# Schematic.net
KiCad netlist of a schematic drawn in EAGLE
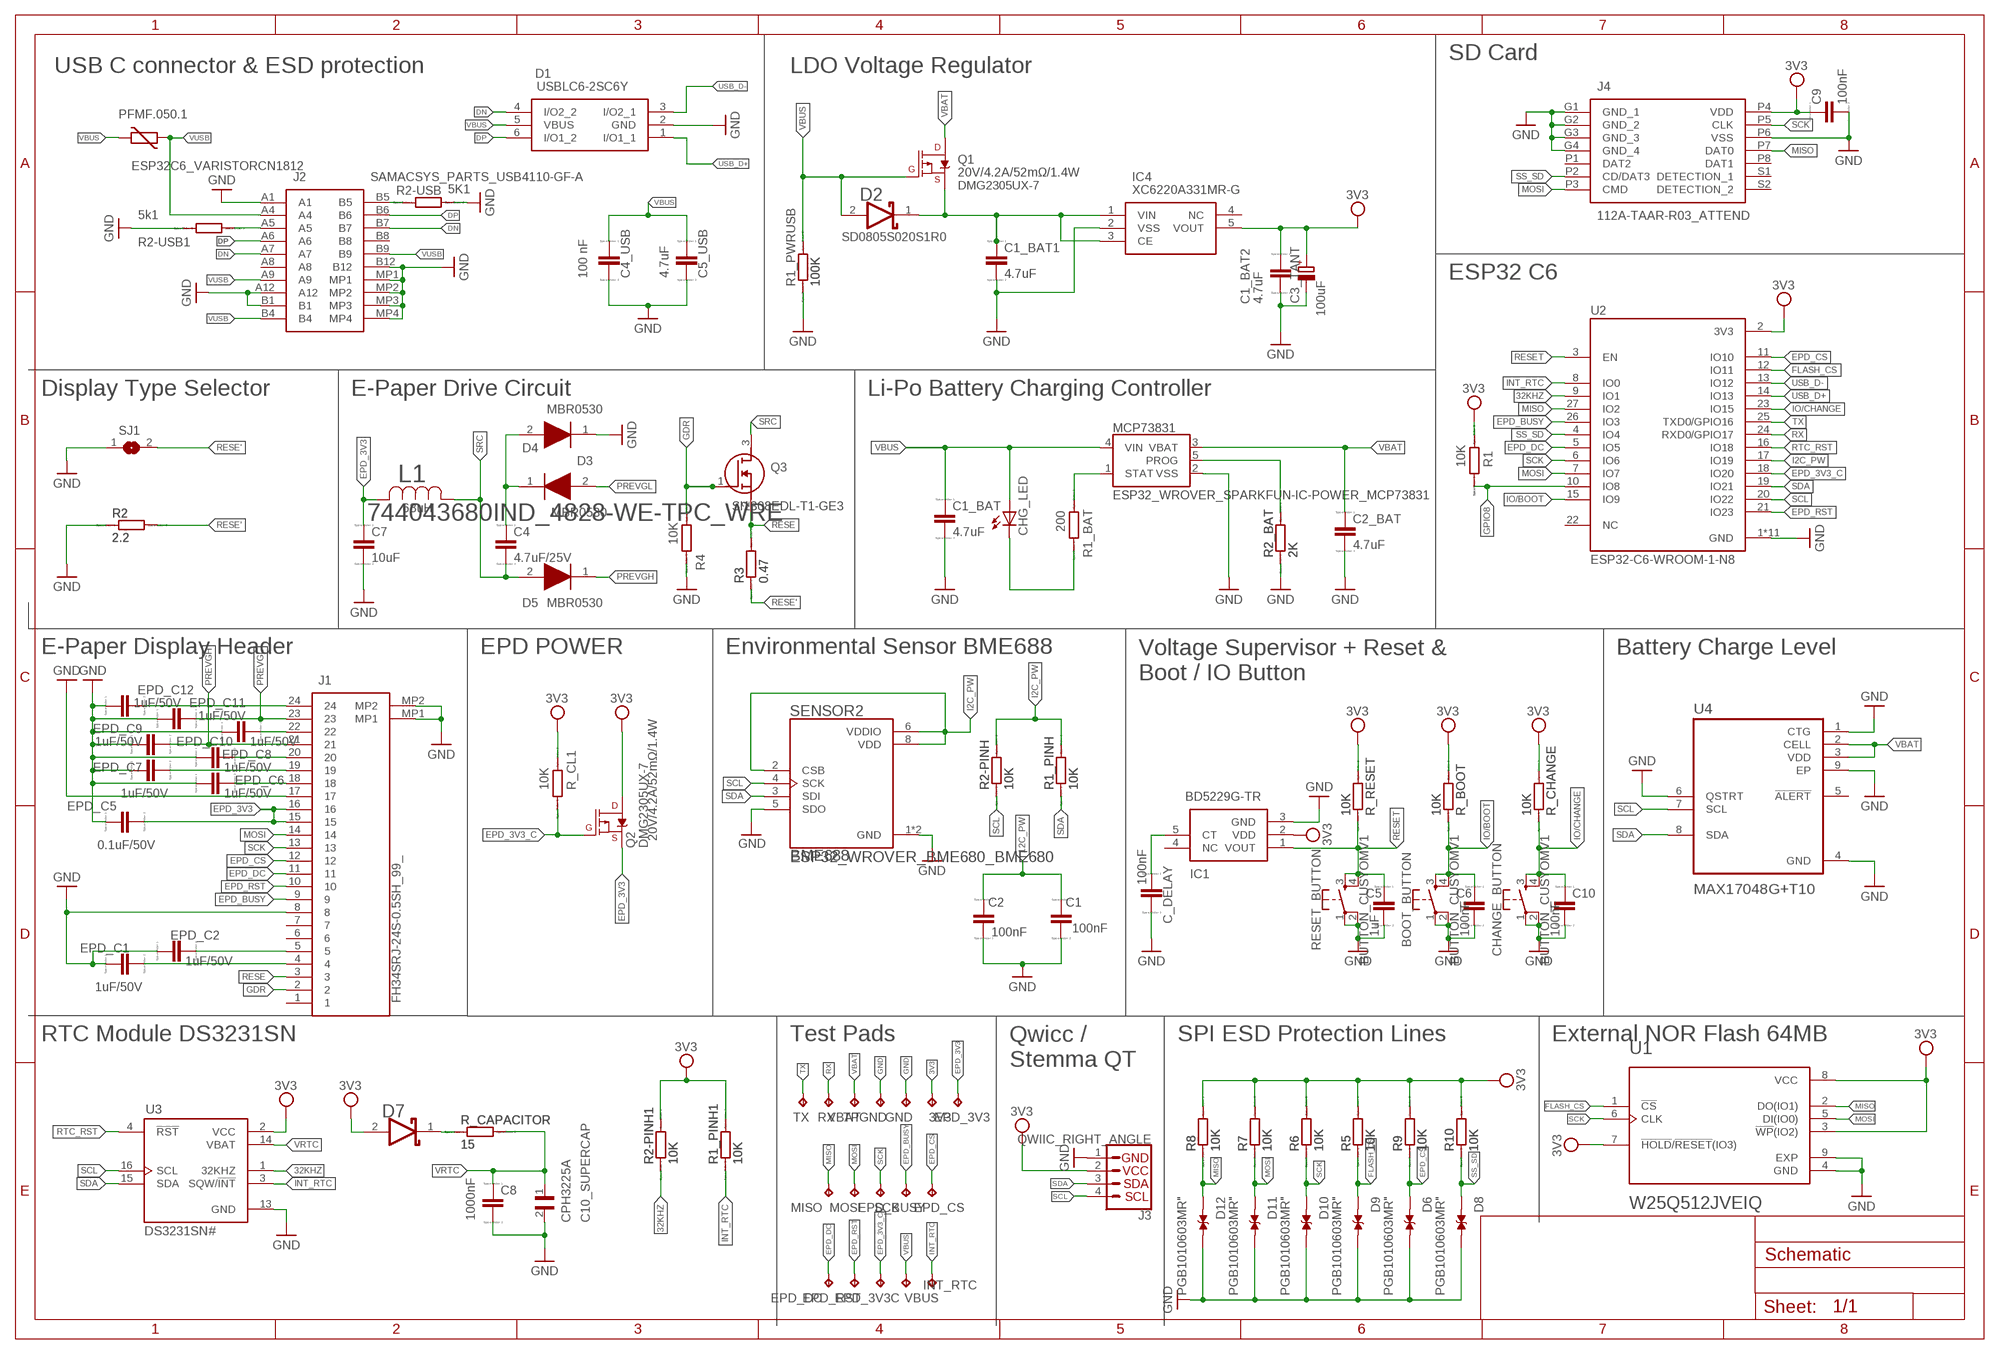
[diagram p0: schematic, sheet 1]

(export (version "E")
  (design (tool "Eeschema 10.0.6"))
  (components
    (comp (ref "3V3")
      (value "TPTP20R")
      (footprint "eagle-import:TP20R")
      (libsource (lib "eagle-import") (part "TPTP20R"))
    )
    (comp (ref "BOOT_BUTTON")
      (value "BUTTON_CUSYOMV1")
      (footprint "eagle-import:MYBUTTON")
      (libsource (lib "eagle-import") (part "BUTTON_CUSYOMV1"))
    )
    (comp (ref "C1")
      (value "100nF")
      (footprint "eagle-import:ESP32_WROVER_EAGLE-LTSPICE_C0402")
      (libsource (lib "eagle-import") (part "ESP32_WROVER_EAGLE-LTSPICE_CC0402"))
    )
    (comp (ref "C1_BAT")
      (value "4.7uF")
      (footprint "eagle-import:EAGLE-LTSPICE_C0402")
      (libsource (lib "eagle-import") (part "EAGLE-LTSPICE_CC0402"))
    )
    (comp (ref "C1_BAT1")
      (value "4.7uF")
      (footprint "eagle-import:EAGLE-LTSPICE_C0402")
      (libsource (lib "eagle-import") (part "EAGLE-LTSPICE_CC0402"))
    )
    (comp (ref "C1_BAT2")
      (value "4.7uF")
      (footprint "eagle-import:EAGLE-LTSPICE_C0402")
      (libsource (lib "eagle-import") (part "EAGLE-LTSPICE_CC0402"))
    )
    (comp (ref "C2")
      (value "100nF")
      (footprint "eagle-import:ESP32_WROVER_EAGLE-LTSPICE_C0402")
      (libsource (lib "eagle-import") (part "ESP32_WROVER_EAGLE-LTSPICE_CC0402"))
    )
    (comp (ref "C2_BAT")
      (value "4.7uF")
      (footprint "eagle-import:EAGLE-LTSPICE_C0402")
      (libsource (lib "eagle-import") (part "EAGLE-LTSPICE_CC0402"))
    )
    (comp (ref "C3_TANT")
      (value "100uF")
      (footprint "eagle-import:RCL_CT3528")
      (libsource (lib "eagle-import") (part "RCL_CPOL-EUCT3528"))
    )
    (comp (ref "C4")
      (value "4.7uF/25V")
      (footprint "eagle-import:EAGLE-LTSPICE_C0402")
      (libsource (lib "eagle-import") (part "EAGLE-LTSPICE_CC0402"))
    )
    (comp (ref "C4_USB")
      (value "100 nF")
      (footprint "eagle-import:ESP32_WROVER_EAGLE-LTSPICE_C0402")
      (libsource (lib "eagle-import") (part "ESP32_WROVER_EAGLE-LTSPICE_CC0402"))
    )
    (comp (ref "C5")
      (value "1uF")
      (footprint "eagle-import:EAGLE-LTSPICE_C0402")
      (libsource (lib "eagle-import") (part "EAGLE-LTSPICE_CC0402"))
    )
    (comp (ref "C5_USB")
      (value "4.7uF")
      (footprint "eagle-import:ESP32_WROVER_EAGLE-LTSPICE_C0402")
      (libsource (lib "eagle-import") (part "ESP32_WROVER_EAGLE-LTSPICE_CC0402"))
    )
    (comp (ref "C6")
      (value "100nF")
      (footprint "eagle-import:EAGLE-LTSPICE_C0402")
      (libsource (lib "eagle-import") (part "EAGLE-LTSPICE_CC0402"))
    )
    (comp (ref "C7")
      (value "10uF")
      (footprint "eagle-import:EAGLE-LTSPICE_C0402")
      (libsource (lib "eagle-import") (part "EAGLE-LTSPICE_CC0402"))
    )
    (comp (ref "C8")
      (value "1000nF")
      (footprint "eagle-import:EAGLE-LTSPICE_C0402")
      (libsource (lib "eagle-import") (part "EAGLE-LTSPICE_CC0402"))
    )
    (comp (ref "C9")
      (value "100nF")
      (footprint "eagle-import:EAGLE-LTSPICE_C0402")
      (libsource (lib "eagle-import") (part "EAGLE-LTSPICE_CC0402"))
    )
    (comp (ref "C10")
      (value "100nF")
      (footprint "eagle-import:EAGLE-LTSPICE_C0402")
      (libsource (lib "eagle-import") (part "EAGLE-LTSPICE_CC0402"))
    )
    (comp (ref "C10_SUPERCAP")
      (value "CPH3225A")
      (footprint "eagle-import:CAPCP3225X100N")
      (fields (field (name "MF") "Seiko Instruments"))
      (libsource (lib "eagle-import") (part "CPH3225A"))
    )
    (comp (ref "CHANGE_BUTTON")
      (value "BUTTON_CUSYOMV1")
      (footprint "eagle-import:MYBUTTON")
      (libsource (lib "eagle-import") (part "BUTTON_CUSYOMV1"))
    )
    (comp (ref "CHG_LED")
      (value "ADAFRUIT_LEDCHIP-LED0603")
      (footprint "eagle-import:ADAFRUIT_CHIP-LED0603")
      (libsource (lib "eagle-import") (part "ADAFRUIT_LEDCHIP-LED0603"))
    )
    (comp (ref "C_DELAY")
      (value "100nF")
      (footprint "eagle-import:EAGLE-LTSPICE_C0402")
      (libsource (lib "eagle-import") (part "EAGLE-LTSPICE_CC0402"))
    )
    (comp (ref "D1")
      (value "USBLC6-2SC6Y")
      (footprint "eagle-import:SOT95P280X145-6N")
      (fields (field (name "MF") "STMicroelectronics"))
      (libsource (lib "eagle-import") (part "USBLC6-2SC6Y"))
    )
    (comp (ref "D2")
      (value "ESP32_WROVER_AVX---SD0805S020S1R0_AVX_SD0805S020S1R0_0_0AVX_SD0805S020S1R0_0_0")
      (footprint "eagle-import:ESP32_WROVER_AVX---SD0805S020S1R0_AVX_SD0805S020S1R0_0")
      (fields
        (field (name "DIGIKEY_PART_NUMBER") "478-7800-1-ND")
        (field (name "MF") "AVX")
        (field (name "MOUSER_PART_NUMBER") "581-SD0805S020S1R0")
      )
      (libsource (lib "eagle-import") (part "ESP32_WROVER_AVX---SD0805S020S1R0_AVX_SD0805S020S1R0_0_0AVX_SD0805S020S1R0_0_0"))
    )
    (comp (ref "D3")
      (value "MBR0530")
      (footprint "eagle-import:SOD3716X135N")
      (fields (field (name "MF") "ON Semiconductor"))
      (libsource (lib "eagle-import") (part "MBR0530"))
    )
    (comp (ref "D4")
      (value "MBR0530")
      (footprint "eagle-import:SOD3716X135N")
      (fields (field (name "MF") "ON Semiconductor"))
      (libsource (lib "eagle-import") (part "MBR0530"))
    )
    (comp (ref "D5")
      (value "MBR0530")
      (footprint "eagle-import:SOD3716X135N")
      (fields (field (name "MF") "ON Semiconductor"))
      (libsource (lib "eagle-import") (part "MBR0530"))
    )
    (comp (ref "D6")
      (value "PGB1010603MR\"")
      (footprint "eagle-import:DIOC1608X36N")
      (libsource (lib "eagle-import") (part "PGB1010603MR{dblquote}"))
    )
    (comp (ref "D7")
      (value "ESP32_WROVER_AVX---SD0805S020S1R0_AVX_SD0805S020S1R0_0_0AVX_SD0805S020S1R0_0_0")
      (footprint "eagle-import:ESP32_WROVER_AVX---SD0805S020S1R0_AVX_SD0805S020S1R0_0")
      (fields
        (field (name "DIGIKEY_PART_NUMBER") "478-7800-1-ND")
        (field (name "MF") "AVX")
        (field (name "MOUSER_PART_NUMBER") "581-SD0805S020S1R0")
      )
      (libsource (lib "eagle-import") (part "ESP32_WROVER_AVX---SD0805S020S1R0_AVX_SD0805S020S1R0_0_0AVX_SD0805S020S1R0_0_0"))
    )
    (comp (ref "D8")
      (value "PGB1010603MR\"")
      (footprint "eagle-import:DIOC1608X36N")
      (libsource (lib "eagle-import") (part "PGB1010603MR{dblquote}"))
    )
    (comp (ref "D9")
      (value "PGB1010603MR\"")
      (footprint "eagle-import:DIOC1608X36N")
      (libsource (lib "eagle-import") (part "PGB1010603MR{dblquote}"))
    )
    (comp (ref "D10")
      (value "PGB1010603MR\"")
      (footprint "eagle-import:DIOC1608X36N")
      (libsource (lib "eagle-import") (part "PGB1010603MR{dblquote}"))
    )
    (comp (ref "D11")
      (value "PGB1010603MR\"")
      (footprint "eagle-import:DIOC1608X36N")
      (libsource (lib "eagle-import") (part "PGB1010603MR{dblquote}"))
    )
    (comp (ref "D12")
      (value "PGB1010603MR\"")
      (footprint "eagle-import:DIOC1608X36N")
      (libsource (lib "eagle-import") (part "PGB1010603MR{dblquote}"))
    )
    (comp (ref "EPD_3V3")
      (value "TPTP20R")
      (footprint "eagle-import:TP20R")
      (libsource (lib "eagle-import") (part "TPTP20R"))
    )
    (comp (ref "EPD_3V3C")
      (value "TPTP20R")
      (footprint "eagle-import:TP20R")
      (libsource (lib "eagle-import") (part "TPTP20R"))
    )
    (comp (ref "EPD_BUSY")
      (value "TPTP20R")
      (footprint "eagle-import:TP20R")
      (libsource (lib "eagle-import") (part "TPTP20R"))
    )
    (comp (ref "EPD_C1")
      (value "1uF/50V")
      (footprint "eagle-import:EAGLE-LTSPICE_C0402")
      (libsource (lib "eagle-import") (part "EAGLE-LTSPICE_CC0402"))
    )
    (comp (ref "EPD_C2")
      (value "1uF/50V")
      (footprint "eagle-import:EAGLE-LTSPICE_C0402")
      (libsource (lib "eagle-import") (part "EAGLE-LTSPICE_CC0402"))
    )
    (comp (ref "EPD_C5")
      (value "0.1uF/50V")
      (footprint "eagle-import:EAGLE-LTSPICE_C0402")
      (libsource (lib "eagle-import") (part "EAGLE-LTSPICE_CC0402"))
    )
    (comp (ref "EPD_C6")
      (value "1uF/50V")
      (footprint "eagle-import:EAGLE-LTSPICE_C0402")
      (libsource (lib "eagle-import") (part "EAGLE-LTSPICE_CC0402"))
    )
    (comp (ref "EPD_C7")
      (value "1uF/50V")
      (footprint "eagle-import:EAGLE-LTSPICE_C0402")
      (libsource (lib "eagle-import") (part "EAGLE-LTSPICE_CC0402"))
    )
    (comp (ref "EPD_C8")
      (value "1uF/50V")
      (footprint "eagle-import:EAGLE-LTSPICE_C0402")
      (libsource (lib "eagle-import") (part "EAGLE-LTSPICE_CC0402"))
    )
    (comp (ref "EPD_C9")
      (value "1uF/50V")
      (footprint "eagle-import:EAGLE-LTSPICE_C0402")
      (libsource (lib "eagle-import") (part "EAGLE-LTSPICE_CC0402"))
    )
    (comp (ref "EPD_C10")
      (value "1uF/50V")
      (footprint "eagle-import:EAGLE-LTSPICE_C0402")
      (libsource (lib "eagle-import") (part "EAGLE-LTSPICE_CC0402"))
    )
    (comp (ref "EPD_C11")
      (value "1uF/50V")
      (footprint "eagle-import:EAGLE-LTSPICE_C0402")
      (libsource (lib "eagle-import") (part "EAGLE-LTSPICE_CC0402"))
    )
    (comp (ref "EPD_C12")
      (value "1uF/50V")
      (footprint "eagle-import:EAGLE-LTSPICE_C0402")
      (libsource (lib "eagle-import") (part "EAGLE-LTSPICE_CC0402"))
    )
    (comp (ref "EPD_CS")
      (value "TPTP20R")
      (footprint "eagle-import:TP20R")
      (libsource (lib "eagle-import") (part "TPTP20R"))
    )
    (comp (ref "EPD_DC")
      (value "TPTP20R")
      (footprint "eagle-import:TP20R")
      (libsource (lib "eagle-import") (part "TPTP20R"))
    )
    (comp (ref "EPD_RST")
      (value "TPTP20R")
      (footprint "eagle-import:TP20R")
      (libsource (lib "eagle-import") (part "TPTP20R"))
    )
    (comp (ref "GND")
      (value "TPTP20R")
      (footprint "eagle-import:TP20R")
      (libsource (lib "eagle-import") (part "TPTP20R"))
    )
    (comp (ref "IC1")
      (value "BD5229G-TR")
      (footprint "eagle-import:SOT95P280X125-5N")
      (fields (field (name "MOUSER_PART_NUMBER") "755-BD5229G-TR"))
      (libsource (lib "eagle-import") (part "BD5229G-TR"))
    )
    (comp (ref "IC4")
      (value "XC6220A331MR-G")
      (footprint "eagle-import:SOT95P280X120-5N")
      (fields (field (name "MOUSER_PART_NUMBER") "865-XC6220A331MR-G"))
      (libsource (lib "eagle-import") (part "XC6220A331MR-G"))
    )
    (comp (ref "INT_RTC")
      (value "TPTP20R")
      (footprint "eagle-import:TP20R")
      (libsource (lib "eagle-import") (part "TPTP20R"))
    )
    (comp (ref "J1")
      (value "FH34SRJ-24S-0.5SH_99_")
      (footprint "eagle-import:FH34SRJ24S05SH99")
      (fields
        (field (name "MANUFACTURER_PART_NUMBER") "FH34SRJ-24S-0.5SH(99)")
        (field (name "MOUSER_PART_NUMBER") "798-FH34SRJ24S05SH99")
      )
      (libsource (lib "eagle-import") (part "FH34SRJ-24S-0.5SH_99_"))
    )
    (comp (ref "J2")
      (value "SAMACSYS_PARTS_USB4110-GF-A")
      (footprint "eagle-import:SAMACSYS_PARTS_USB4110GFA")
      (fields
        (field (name "MANUFACTURER_PART_NUMBER") "USB4110-GF-A")
        (field (name "MOUSER_PART_NUMBER") "640-USB4110-GF-A")
      )
      (libsource (lib "eagle-import") (part "SAMACSYS_PARTS_USB4110-GF-A"))
    )
    (comp (ref "J3")
      (value "QWIIC_RIGHT_ANGLE")
      (footprint "eagle-import:JST04_1MM_RA")
      (libsource (lib "eagle-import") (part "QWIIC_CONNECTORJS-1MM"))
    )
    (comp (ref "J4")
      (value "112A-TAAR-R03_ATTEND")
      (footprint "eagle-import:112ATAARR03ATTEND")
      (fields (field (name "MANUFACTURER_PART_NUMBER") "112A-TAAR-R03 ATTEND"))
      (libsource (lib "eagle-import") (part "112A-TAAR-R03_ATTEND"))
    )
    (comp (ref "L1")
      (value "744043680IND_4828-WE-TPC_WRE")
      (footprint "eagle-import:IND_4828-WE-TPC_WRE")
      (fields
        (field (name "MANUFACTURER_PART_NUMBER") "744043680")
        (field (name "L1") "68uH")
        (field (name "COPYRIGHT") "Copyright (C) 2024 Ultra Librarian. All rights reserved.")
      )
      (libsource (lib "eagle-import") (part "744043680IND_4828-WE-TPC_WRE"))
    )
    (comp (ref "MCP73831")
      (value "ESP32_WROVER_SPARKFUN-IC-POWER_MCP73831")
      (footprint "eagle-import:ESP32_WROVER_SPARKFUN-IC-POWER_SOT23-5")
      (libsource (lib "eagle-import") (part "ESP32_WROVER_SPARKFUN-IC-POWER_MCP73831"))
    )
    (comp (ref "MISO")
      (value "TPTP20R")
      (footprint "eagle-import:TP20R")
      (libsource (lib "eagle-import") (part "TPTP20R"))
    )
    (comp (ref "MOSI")
      (value "TPTP20R")
      (footprint "eagle-import:TP20R")
      (libsource (lib "eagle-import") (part "TPTP20R"))
    )
    (comp (ref "PFMF.050.1")
      (value "ESP32C6_VARISTORCN1812")
      (footprint "eagle-import:ESP32C6_VARISTOR_CT_CN1812")
      (libsource (lib "eagle-import") (part "ESP32C6_VARISTORCN1812"))
    )
    (comp (ref "Q1")
      (value "20V/4.2A/52mΩ/1.4W")
      (footprint "eagle-import:ESP32_WROVER_SPARKFUN-DISCRETESEMI_SOT23-3")
      (libsource (lib "eagle-import") (part "ESP32_WROVER_SPARKFUN-DISCRETESEMI_MOSFET_PCH-DMG2305UX-7"))
    )
    (comp (ref "Q2")
      (value "20V/4.2A/52mΩ/1.4W")
      (footprint "eagle-import:ESP32_WROVER_SPARKFUN-DISCRETESEMI_SOT23-3")
      (libsource (lib "eagle-import") (part "ESP32_WROVER_SPARKFUN-DISCRETESEMI_MOSFET_PCH-DMG2305UX-7"))
    )
    (comp (ref "Q3")
      (value "SI1308EDL-T1-GE3")
      (footprint "eagle-import:SOT65P210X110-3N")
      (fields (field (name "MF") "Vishay Siliconix"))
      (libsource (lib "eagle-import") (part "SI1308EDL-T1-GE3"))
    )
    (comp (ref "R1")
      (value "10K")
      (footprint "eagle-import:ESP32_WROVER_EAGLE-LTSPICE_R0402")
      (libsource (lib "eagle-import") (part "ESP32_WROVER_EAGLE-LTSPICE_RR0402"))
    )
    (comp (ref "R1_BAT")
      (value "200")
      (footprint "eagle-import:ESP32_WROVER_EAGLE-LTSPICE_R0402")
      (libsource (lib "eagle-import") (part "ESP32_WROVER_EAGLE-LTSPICE_RR0402"))
    )
    (comp (ref "R1_PINH")
      (value "10K")
      (footprint "eagle-import:ESP32_WROVER_EAGLE-LTSPICE_R0402")
      (libsource (lib "eagle-import") (part "ESP32_WROVER_EAGLE-LTSPICE_RR0402"))
    )
    (comp (ref "R1_PINH1")
      (value "10K")
      (footprint "eagle-import:ESP32_WROVER_EAGLE-LTSPICE_R0402")
      (libsource (lib "eagle-import") (part "ESP32_WROVER_EAGLE-LTSPICE_RR0402"))
    )
    (comp (ref "R1_PWRUSB")
      (value "100K")
      (footprint "eagle-import:ESP32_WROVER_EAGLE-LTSPICE_R0402")
      (libsource (lib "eagle-import") (part "ESP32_WROVER_EAGLE-LTSPICE_RR0402"))
    )
    (comp (ref "R2")
      (value "2.2")
      (footprint "eagle-import:ESP32_WROVER_EAGLE-LTSPICE_R0402")
      (libsource (lib "eagle-import") (part "ESP32_WROVER_EAGLE-LTSPICE_RR0402"))
    )
    (comp (ref "R2-PINH")
      (value "10K")
      (footprint "eagle-import:ESP32_WROVER_EAGLE-LTSPICE_R0402")
      (libsource (lib "eagle-import") (part "ESP32_WROVER_EAGLE-LTSPICE_RR0402"))
    )
    (comp (ref "R2-PINH1")
      (value "10K")
      (footprint "eagle-import:ESP32_WROVER_EAGLE-LTSPICE_R0402")
      (libsource (lib "eagle-import") (part "ESP32_WROVER_EAGLE-LTSPICE_RR0402"))
    )
    (comp (ref "R2-USB")
      (value "5K1")
      (footprint "eagle-import:ESP32_WROVER_EAGLE-LTSPICE_R0402")
      (libsource (lib "eagle-import") (part "ESP32_WROVER_EAGLE-LTSPICE_RR0402"))
    )
    (comp (ref "R2-USB1")
      (value "5k1")
      (footprint "eagle-import:ESP32_WROVER_EAGLE-LTSPICE_R0402")
      (libsource (lib "eagle-import") (part "ESP32_WROVER_EAGLE-LTSPICE_RR0402"))
    )
    (comp (ref "R2_BAT")
      (value "2K")
      (footprint "eagle-import:ESP32_WROVER_EAGLE-LTSPICE_R0402")
      (libsource (lib "eagle-import") (part "ESP32_WROVER_EAGLE-LTSPICE_RR0402"))
    )
    (comp (ref "R3")
      (value "0.47")
      (footprint "eagle-import:ESP32_WROVER_EAGLE-LTSPICE_R0402")
      (libsource (lib "eagle-import") (part "ESP32_WROVER_EAGLE-LTSPICE_RR0402"))
    )
    (comp (ref "R4")
      (value "10K")
      (footprint "eagle-import:ESP32_WROVER_EAGLE-LTSPICE_R0402")
      (libsource (lib "eagle-import") (part "ESP32_WROVER_EAGLE-LTSPICE_RR0402"))
    )
    (comp (ref "R5")
      (value "10K")
      (footprint "eagle-import:ESP32_WROVER_EAGLE-LTSPICE_R0402")
      (libsource (lib "eagle-import") (part "ESP32_WROVER_EAGLE-LTSPICE_RR0402"))
    )
    (comp (ref "R6")
      (value "10K")
      (footprint "eagle-import:ESP32_WROVER_EAGLE-LTSPICE_R0402")
      (libsource (lib "eagle-import") (part "ESP32_WROVER_EAGLE-LTSPICE_RR0402"))
    )
    (comp (ref "R7")
      (value "10K")
      (footprint "eagle-import:ESP32_WROVER_EAGLE-LTSPICE_R0402")
      (libsource (lib "eagle-import") (part "ESP32_WROVER_EAGLE-LTSPICE_RR0402"))
    )
    (comp (ref "R8")
      (value "10K")
      (footprint "eagle-import:ESP32_WROVER_EAGLE-LTSPICE_R0402")
      (libsource (lib "eagle-import") (part "ESP32_WROVER_EAGLE-LTSPICE_RR0402"))
    )
    (comp (ref "R9")
      (value "10K")
      (footprint "eagle-import:ESP32_WROVER_EAGLE-LTSPICE_R0402")
      (libsource (lib "eagle-import") (part "ESP32_WROVER_EAGLE-LTSPICE_RR0402"))
    )
    (comp (ref "R10")
      (value "10K")
      (footprint "eagle-import:ESP32_WROVER_EAGLE-LTSPICE_R0402")
      (libsource (lib "eagle-import") (part "ESP32_WROVER_EAGLE-LTSPICE_RR0402"))
    )
    (comp (ref "RESET_BUTTON")
      (value "BUTTON_CUSYOMV1")
      (footprint "eagle-import:MYBUTTON")
      (libsource (lib "eagle-import") (part "BUTTON_CUSYOMV1"))
    )
    (comp (ref "RX")
      (value "TPTP20R")
      (footprint "eagle-import:TP20R")
      (libsource (lib "eagle-import") (part "TPTP20R"))
    )
    (comp (ref "R_BOOT")
      (value "10K")
      (footprint "eagle-import:ESP32_WROVER_EAGLE-LTSPICE_R0402")
      (libsource (lib "eagle-import") (part "ESP32_WROVER_EAGLE-LTSPICE_RR0402"))
    )
    (comp (ref "R_CAPACITOR")
      (value "15")
      (footprint "eagle-import:ESP32_WROVER_EAGLE-LTSPICE_R0402")
      (libsource (lib "eagle-import") (part "ESP32_WROVER_EAGLE-LTSPICE_RR0402"))
    )
    (comp (ref "R_CHANGE")
      (value "10K")
      (footprint "eagle-import:ESP32_WROVER_EAGLE-LTSPICE_R0402")
      (libsource (lib "eagle-import") (part "ESP32_WROVER_EAGLE-LTSPICE_RR0402"))
    )
    (comp (ref "R_CL1")
      (value "10K")
      (footprint "eagle-import:ESP32_WROVER_EAGLE-LTSPICE_R0402")
      (libsource (lib "eagle-import") (part "ESP32_WROVER_EAGLE-LTSPICE_RR0402"))
    )
    (comp (ref "R_RESET")
      (value "10K")
      (footprint "eagle-import:ESP32_WROVER_EAGLE-LTSPICE_R0402")
      (libsource (lib "eagle-import") (part "ESP32_WROVER_EAGLE-LTSPICE_RR0402"))
    )
    (comp (ref "SCK")
      (value "TPTP20R")
      (footprint "eagle-import:TP20R")
      (libsource (lib "eagle-import") (part "TPTP20R"))
    )
    (comp (ref "SENSOR2")
      (value "ESP32_WROVER_BME680_BME680")
      (footprint "eagle-import:ESP32_WROVER_BME680_PSON80P300X300X100-8N")
      (fields (field (name "MF") "Bosch Sensortec") (field (name "MP") "BME680"))
      (libsource (lib "eagle-import") (part "ESP32_WROVER_BME680_BME680"))
    )
    (comp (ref "SJ1") (value "SJ") (footprint "eagle-import:SJ") (libsource (lib "eagle-import") (part "SJ")))
    (comp (ref "TPGND")
      (value "TPTP20R")
      (footprint "eagle-import:TP20R")
      (libsource (lib "eagle-import") (part "TPTP20R"))
    )
    (comp (ref "TX")
      (value "TPTP20R")
      (footprint "eagle-import:TP20R")
      (libsource (lib "eagle-import") (part "TPTP20R"))
    )
    (comp (ref "U1")
      (value "W25Q512JVEIQ")
      (footprint "eagle-import:SON127P600X800X80-9N")
      (fields (field (name "MF") "Winbond Electronics"))
      (libsource (lib "eagle-import") (part "W25Q512JVEIQ"))
    )
    (comp (ref "U2")
      (value "ESP32-C6-WROOM-1-N8")
      (footprint "eagle-import:XCVR_ESP32-C6-WROOM-1-N8")
      (fields (field (name "MF") "Espressif Systems"))
      (libsource (lib "eagle-import") (part "ESP32-C6-WROOM-1-N8"))
    )
    (comp (ref "U3")
      (value "DS3231SN#")
      (footprint "eagle-import:SOIC127P1032X265-16N")
      (fields (field (name "MF") "Analog Devices"))
      (libsource (lib "eagle-import") (part "DS3231SN#"))
    )
    (comp (ref "U4")
      (value "MAX17048G+T10")
      (footprint "eagle-import:SON50P200X200X80-9N")
      (fields (field (name "MF") "Analog Devices"))
      (libsource (lib "eagle-import") (part "MAX17048G+T10"))
    )
    (comp (ref "VBAT")
      (value "TPTP20R")
      (footprint "eagle-import:TP20R")
      (libsource (lib "eagle-import") (part "TPTP20R"))
    )
    (comp (ref "VBUS")
      (value "TPTP20R")
      (footprint "eagle-import:TP20R")
      (libsource (lib "eagle-import") (part "TPTP20R"))
    )
  )
  (nets
    (net (code "1") (name "/DMG2305UX-7") (class "Default")
      (node (ref "C1_BAT1") (pin "1") (pinfunction "1_1") (pintype "passive"))
      (node (ref "D2") (pin "1") (pinfunction "CATHODE_1") (pintype "bidirectional"))
      (node (ref "IC4") (pin "1") (pinfunction "VIN_1") (pintype "bidirectional"))
      (node (ref "IC4") (pin "3") (pinfunction "CE_3") (pintype "bidirectional"))
      (node (ref "Q1") (pin "2") (pinfunction "S_2") (pintype "bidirectional"))
    )
    (net (code "2") (name "3V3") (class "Default")
      (node (ref "3V3") (pin "TP") (pinfunction "TP_TP") (pintype "input"))
      (node (ref "C1_BAT2") (pin "1") (pinfunction "1_1") (pintype "passive"))
      (node (ref "C3_TANT") (pin "+") (pinfunction "+_+") (pintype "passive"))
      (node (ref "C9") (pin "1") (pinfunction "1_1") (pintype "passive"))
      (node (ref "D7") (pin "2") (pinfunction "ANODE_2") (pintype "bidirectional"))
      (node (ref "IC1") (pin "2") (pinfunction "VDD_2") (pintype "bidirectional"))
      (node (ref "IC4") (pin "5") (pinfunction "VOUT_5") (pintype "bidirectional"))
      (node (ref "J3") (pin "2") (pinfunction "2_2") (pintype "power_in"))
      (node (ref "J4") (pin "P4") (pinfunction "VDD_P4") (pintype "bidirectional"))
      (node (ref "Q2") (pin "3") (pinfunction "D_3") (pintype "bidirectional"))
      (node (ref "R1") (pin "2") (pinfunction "2_2") (pintype "passive"))
      (node (ref "R10") (pin "2") (pinfunction "2_2") (pintype "passive"))
      (node (ref "R1_PINH1") (pin "2") (pinfunction "2_2") (pintype "passive"))
      (node (ref "R2-PINH1") (pin "2") (pinfunction "2_2") (pintype "passive"))
      (node (ref "R5") (pin "2") (pinfunction "2_2") (pintype "passive"))
      (node (ref "R6") (pin "2") (pinfunction "2_2") (pintype "passive"))
      (node (ref "R7") (pin "2") (pinfunction "2_2") (pintype "passive"))
      (node (ref "R8") (pin "2") (pinfunction "2_2") (pintype "passive"))
      (node (ref "R9") (pin "2") (pinfunction "2_2") (pintype "passive"))
      (node (ref "R_BOOT") (pin "2") (pinfunction "2_2") (pintype "passive"))
      (node (ref "R_CHANGE") (pin "2") (pinfunction "2_2") (pintype "passive"))
      (node (ref "R_CL1") (pin "2") (pinfunction "2_2") (pintype "passive"))
      (node (ref "R_RESET") (pin "2") (pinfunction "2_2") (pintype "passive"))
      (node (ref "U1") (pin "3") (pinfunction "~{WP}(IO2)_3") (pintype "bidirectional"))
      (node (ref "U1") (pin "7") (pinfunction "~{HOLD}/~{RESET}(IO3)_7") (pintype "bidirectional"))
      (node (ref "U1") (pin "8") (pinfunction "VCC_8") (pintype "power_in"))
      (node (ref "U2") (pin "2") (pinfunction "3V3_2") (pintype "power_in"))
      (node (ref "U3") (pin "2") (pinfunction "VCC_2") (pintype "power_in"))
    )
    (net (code "3") (name "12C_PW") (class "Default")
      (node (ref "C1") (pin "1") (pinfunction "1_1") (pintype "passive"))
      (node (ref "C2") (pin "1") (pinfunction "1_1") (pintype "passive"))
    )
    (net (code "4") (name "32KHZ") (class "Default")
      (node (ref "R2-PINH1") (pin "1") (pinfunction "1_1") (pintype "passive"))
      (node (ref "U2") (pin "9") (pinfunction "IO1_9") (pintype "bidirectional"))
      (node (ref "U3") (pin "1") (pinfunction "32KHZ_1") (pintype "output"))
    )
    (net (code "5") (name "DN") (class "Default")
      (node (ref "D1") (pin "4") (pinfunction "I/O2_2_4") (pintype "bidirectional"))
      (node (ref "J2") (pin "A7") (pinfunction "A7_A7") (pintype "bidirectional"))
      (node (ref "J2") (pin "B7") (pinfunction "B7_B7") (pintype "bidirectional"))
    )
    (net (code "6") (name "DP") (class "Default")
      (node (ref "D1") (pin "6") (pinfunction "I/O1_2_6") (pintype "bidirectional"))
      (node (ref "J2") (pin "A6") (pinfunction "A6_A6") (pintype "bidirectional"))
      (node (ref "J2") (pin "B6") (pinfunction "B6_B6") (pintype "bidirectional"))
    )
    (net (code "7") (name "EPD_3V3") (class "Default")
      (node (ref "C7") (pin "1") (pinfunction "1_1") (pintype "passive"))
      (node (ref "EPD_3V3") (pin "TP") (pinfunction "TP_TP") (pintype "input"))
      (node (ref "EPD_C5") (pin "2") (pinfunction "2_2") (pintype "passive"))
      (node (ref "J1") (pin "15") (pinfunction "15_15") (pintype "bidirectional"))
      (node (ref "J1") (pin "16") (pinfunction "16_16") (pintype "bidirectional"))
      (node (ref "L1") (pin "2") (pinfunction "2_2") (pintype "passive"))
      (node (ref "Q2") (pin "2") (pinfunction "S_2") (pintype "bidirectional"))
    )
    (net (code "8") (name "EPD_3V3_C") (class "Default")
      (node (ref "EPD_3V3C") (pin "TP") (pinfunction "TP_TP") (pintype "input"))
      (node (ref "Q2") (pin "1") (pinfunction "G_1") (pintype "bidirectional"))
      (node (ref "R_CL1") (pin "1") (pinfunction "1_1") (pintype "passive"))
      (node (ref "U2") (pin "18") (pinfunction "IO20_18") (pintype "bidirectional"))
    )
    (net (code "9") (name "EPD_BUSY") (class "Default")
      (node (ref "EPD_BUSY") (pin "TP") (pinfunction "TP_TP") (pintype "input"))
      (node (ref "J1") (pin "9") (pinfunction "9_9") (pintype "bidirectional"))
      (node (ref "U2") (pin "26") (pinfunction "IO3_26") (pintype "bidirectional"))
    )
    (net (code "10") (name "EPD_CS") (class "Default")
      (node (ref "D6") (pin "1") (pinfunction "1_1") (pintype "passive"))
      (node (ref "EPD_CS") (pin "TP") (pinfunction "TP_TP") (pintype "input"))
      (node (ref "J1") (pin "12") (pinfunction "12_12") (pintype "bidirectional"))
      (node (ref "R9") (pin "1") (pinfunction "1_1") (pintype "passive"))
      (node (ref "U2") (pin "11") (pinfunction "IO10_11") (pintype "bidirectional"))
    )
    (net (code "11") (name "EPD_DC") (class "Default")
      (node (ref "EPD_DC") (pin "TP") (pinfunction "TP_TP") (pintype "input"))
      (node (ref "J1") (pin "11") (pinfunction "11_11") (pintype "bidirectional"))
      (node (ref "U2") (pin "5") (pinfunction "IO5_5") (pintype "bidirectional"))
    )
    (net (code "12") (name "EPD_RST") (class "Default")
      (node (ref "EPD_RST") (pin "TP") (pinfunction "TP_TP") (pintype "input"))
      (node (ref "J1") (pin "10") (pinfunction "10_10") (pintype "bidirectional"))
      (node (ref "U2") (pin "21") (pinfunction "IO23_21") (pintype "bidirectional"))
    )
    (net (code "13") (name "FLASH_CS") (class "Default")
      (node (ref "D9") (pin "1") (pinfunction "1_1") (pintype "passive"))
      (node (ref "R5") (pin "1") (pinfunction "1_1") (pintype "passive"))
      (node (ref "U1") (pin "1") (pinfunction "~{CS}_1") (pintype "input"))
      (node (ref "U2") (pin "12") (pinfunction "IO11_12") (pintype "bidirectional"))
    )
    (net (code "14") (name "GDR") (class "Default")
      (node (ref "J1") (pin "2") (pinfunction "2_2") (pintype "bidirectional"))
      (node (ref "Q3") (pin "1") (pinfunction "G_1") (pintype "bidirectional"))
      (node (ref "R4") (pin "2") (pinfunction "2_2") (pintype "passive"))
    )
    (net (code "15") (name "GND") (class "Default")
      (node (ref "BOOT_BUTTON") (pin "1") (pinfunction "1_1") (pintype "passive"))
      (node (ref "BOOT_BUTTON") (pin "2") (pinfunction "2_2") (pintype "passive"))
      (node (ref "C1") (pin "2") (pinfunction "2_2") (pintype "passive"))
      (node (ref "C10") (pin "2") (pinfunction "2_2") (pintype "passive"))
      (node (ref "C10_SUPERCAP") (pin "2") (pinfunction "2_2") (pintype "passive"))
      (node (ref "C1_BAT") (pin "2") (pinfunction "2_2") (pintype "passive"))
      (node (ref "C1_BAT1") (pin "2") (pinfunction "2_2") (pintype "passive"))
      (node (ref "C1_BAT2") (pin "2") (pinfunction "2_2") (pintype "passive"))
      (node (ref "C2") (pin "2") (pinfunction "2_2") (pintype "passive"))
      (node (ref "C2_BAT") (pin "2") (pinfunction "2_2") (pintype "passive"))
      (node (ref "C3_TANT") (pin "-") (pinfunction "-_-") (pintype "passive"))
      (node (ref "C4_USB") (pin "2") (pinfunction "2_2") (pintype "passive"))
      (node (ref "C5") (pin "2") (pinfunction "2_2") (pintype "passive"))
      (node (ref "C5_USB") (pin "2") (pinfunction "2_2") (pintype "passive"))
      (node (ref "C6") (pin "2") (pinfunction "2_2") (pintype "passive"))
      (node (ref "C7") (pin "2") (pinfunction "2_2") (pintype "passive"))
      (node (ref "C8") (pin "2") (pinfunction "2_2") (pintype "passive"))
      (node (ref "C9") (pin "2") (pinfunction "2_2") (pintype "passive"))
      (node (ref "CHANGE_BUTTON") (pin "1") (pinfunction "1_1") (pintype "passive"))
      (node (ref "CHANGE_BUTTON") (pin "2") (pinfunction "2_2") (pintype "passive"))
      (node (ref "C_DELAY") (pin "2") (pinfunction "2_2") (pintype "passive"))
      (node (ref "D1") (pin "2") (pinfunction "GND_2") (pintype "bidirectional"))
      (node (ref "D10") (pin "2") (pinfunction "2_2") (pintype "passive"))
      (node (ref "D11") (pin "2") (pinfunction "2_2") (pintype "passive"))
      (node (ref "D12") (pin "2") (pinfunction "2_2") (pintype "passive"))
      (node (ref "D4") (pin "1") (pinfunction "K_1") (pintype "bidirectional"))
      (node (ref "D6") (pin "2") (pinfunction "2_2") (pintype "passive"))
      (node (ref "D8") (pin "2") (pinfunction "2_2") (pintype "passive"))
      (node (ref "D9") (pin "2") (pinfunction "2_2") (pintype "passive"))
      (node (ref "EPD_C1") (pin "1") (pinfunction "1_1") (pintype "passive"))
      (node (ref "EPD_C10") (pin "1") (pinfunction "1_1") (pintype "passive"))
      (node (ref "EPD_C11") (pin "1") (pinfunction "1_1") (pintype "passive"))
      (node (ref "EPD_C12") (pin "1") (pinfunction "1_1") (pintype "passive"))
      (node (ref "EPD_C2") (pin "1") (pinfunction "1_1") (pintype "passive"))
      (node (ref "EPD_C5") (pin "1") (pinfunction "1_1") (pintype "passive"))
      (node (ref "EPD_C6") (pin "1") (pinfunction "1_1") (pintype "passive"))
      (node (ref "EPD_C7") (pin "1") (pinfunction "1_1") (pintype "passive"))
      (node (ref "EPD_C8") (pin "1") (pinfunction "1_1") (pintype "passive"))
      (node (ref "EPD_C9") (pin "1") (pinfunction "1_1") (pintype "passive"))
      (node (ref "GND") (pin "TP") (pinfunction "TP_TP") (pintype "input"))
      (node (ref "IC1") (pin "3") (pinfunction "GND_3") (pintype "bidirectional"))
      (node (ref "IC4") (pin "2") (pinfunction "VSS_2") (pintype "bidirectional"))
      (node (ref "J1") (pin "17") (pinfunction "17_17") (pintype "bidirectional"))
      (node (ref "J1") (pin "8") (pinfunction "8_8") (pintype "bidirectional"))
      (node (ref "J1") (pin "MP1") (pinfunction "MP1_MP1") (pintype "bidirectional"))
      (node (ref "J1") (pin "MP2") (pinfunction "MP2_MP2") (pintype "bidirectional"))
      (node (ref "J2") (pin "A1") (pinfunction "A1_A1") (pintype "bidirectional"))
      (node (ref "J2") (pin "A12") (pinfunction "A12_A12") (pintype "bidirectional"))
      (node (ref "J2") (pin "B1") (pinfunction "B1_B1") (pintype "bidirectional"))
      (node (ref "J2") (pin "B12") (pinfunction "B12_B12") (pintype "bidirectional"))
      (node (ref "J2") (pin "MP1") (pinfunction "MP1_MP1") (pintype "bidirectional"))
      (node (ref "J2") (pin "MP2") (pinfunction "MP2_MP2") (pintype "bidirectional"))
      (node (ref "J2") (pin "MP3") (pinfunction "MP3_MP3") (pintype "bidirectional"))
      (node (ref "J2") (pin "MP4") (pinfunction "MP4_MP4") (pintype "bidirectional"))
      (node (ref "J3") (pin "1") (pinfunction "1_1") (pintype "power_in"))
      (node (ref "J4") (pin "G1") (pinfunction "GND_1_G1") (pintype "bidirectional"))
      (node (ref "J4") (pin "G2") (pinfunction "GND_2_G2") (pintype "bidirectional"))
      (node (ref "J4") (pin "G3") (pinfunction "GND_3_G3") (pintype "bidirectional"))
      (node (ref "J4") (pin "G4") (pinfunction "GND_4_G4") (pintype "bidirectional"))
      (node (ref "J4") (pin "P6") (pinfunction "VSS_P6") (pintype "bidirectional"))
      (node (ref "MCP73831") (pin "2") (pinfunction "VSS_2") (pintype "power_in"))
      (node (ref "R1_PWRUSB") (pin "1") (pinfunction "1_1") (pintype "passive"))
      (node (ref "R2") (pin "1") (pinfunction "1_1") (pintype "passive"))
      (node (ref "R2-USB") (pin "2") (pinfunction "2_2") (pintype "passive"))
      (node (ref "R2-USB1") (pin "1") (pinfunction "1_1") (pintype "passive"))
      (node (ref "R2_BAT") (pin "1") (pinfunction "1_1") (pintype "passive"))
      (node (ref "R4") (pin "1") (pinfunction "1_1") (pintype "passive"))
      (node (ref "RESET_BUTTON") (pin "1") (pinfunction "1_1") (pintype "passive"))
      (node (ref "RESET_BUTTON") (pin "2") (pinfunction "2_2") (pintype "passive"))
      (node (ref "SENSOR2") (pin "1") (pinfunction "GND_1") (pintype "power_in"))
      (node (ref "SENSOR2") (pin "5") (pinfunction "SDO_5") (pintype "bidirectional"))
      (node (ref "SENSOR2") (pin "7") (pinfunction "GND_7") (pintype "power_in"))
      (node (ref "SJ1") (pin "1") (pinfunction "1_1") (pintype "passive"))
      (node (ref "TPGND") (pin "TP") (pinfunction "TP_TP") (pintype "input"))
      (node (ref "U1") (pin "4") (pinfunction "GND_4") (pintype "power_in"))
      (node (ref "U1") (pin "9") (pinfunction "EXP_9") (pintype "passive"))
      (node (ref "U2") (pin "1") (pinfunction "GND_1") (pintype "power_in"))
      (node (ref "U2") (pin "28") (pinfunction "GND_28") (pintype "power_in"))
      (node (ref "U2") (pin "29_1") (pinfunction "GND_29_1") (pintype "power_in"))
      (node (ref "U2") (pin "29_2") (pinfunction "GND_29_2") (pintype "power_in"))
      (node (ref "U2") (pin "29_3") (pinfunction "GND_29_3") (pintype "power_in"))
      (node (ref "U2") (pin "29_4") (pinfunction "GND_29_4") (pintype "power_in"))
      (node (ref "U2") (pin "29_5") (pinfunction "GND_29_5") (pintype "power_in"))
      (node (ref "U2") (pin "29_6") (pinfunction "GND_29_6") (pintype "power_in"))
      (node (ref "U2") (pin "29_7") (pinfunction "GND_29_7") (pintype "power_in"))
      (node (ref "U2") (pin "29_8") (pinfunction "GND_29_8") (pintype "power_in"))
      (node (ref "U2") (pin "29_9") (pinfunction "GND_29_9") (pintype "power_in"))
      (node (ref "U3") (pin "13") (pinfunction "GND_13") (pintype "power_in"))
      (node (ref "U4") (pin "1") (pinfunction "CTG_1") (pintype "power_in"))
      (node (ref "U4") (pin "4") (pinfunction "GND_4") (pintype "power_in"))
      (node (ref "U4") (pin "6") (pinfunction "QSTRT_6") (pintype "input"))
      (node (ref "U4") (pin "9") (pinfunction "EP_9") (pintype "power_in"))
    )
    (net (code "16") (name "GPIO8") (class "Default")
      (node (ref "R1") (pin "1") (pinfunction "1_1") (pintype "passive"))
      (node (ref "U2") (pin "10") (pinfunction "IO8_10") (pintype "bidirectional"))
    )
    (net (code "17") (name "I2C_PW") (class "Default")
      (node (ref "R1_PINH") (pin "2") (pinfunction "2_2") (pintype "passive"))
      (node (ref "R2-PINH") (pin "2") (pinfunction "2_2") (pintype "passive"))
      (node (ref "SENSOR2") (pin "2") (pinfunction "CSB_2") (pintype "input"))
      (node (ref "SENSOR2") (pin "6") (pinfunction "VDDIO_6") (pintype "power_in"))
      (node (ref "SENSOR2") (pin "8") (pinfunction "VDD_8") (pintype "power_in"))
      (node (ref "U2") (pin "17") (pinfunction "IO19_17") (pintype "bidirectional"))
    )
    (net (code "18") (name "INT_RTC") (class "Default")
      (node (ref "INT_RTC") (pin "TP") (pinfunction "TP_TP") (pintype "input"))
      (node (ref "R1_PINH1") (pin "1") (pinfunction "1_1") (pintype "passive"))
      (node (ref "U2") (pin "8") (pinfunction "IO0_8") (pintype "bidirectional"))
      (node (ref "U3") (pin "3") (pinfunction "SQW/~{INT}_3") (pintype "output"))
    )
    (net (code "19") (name "IO{slash}BOOT") (class "Default")
      (node (ref "BOOT_BUTTON") (pin "3") (pinfunction "3_3") (pintype "passive"))
      (node (ref "BOOT_BUTTON") (pin "4") (pinfunction "4_4") (pintype "passive"))
      (node (ref "C6") (pin "1") (pinfunction "1_1") (pintype "passive"))
      (node (ref "R_BOOT") (pin "1") (pinfunction "1_1") (pintype "passive"))
      (node (ref "U2") (pin "15") (pinfunction "IO9_15") (pintype "bidirectional"))
    )
    (net (code "20") (name "IO{slash}CHANGE") (class "Default")
      (node (ref "C10") (pin "1") (pinfunction "1_1") (pintype "passive"))
      (node (ref "CHANGE_BUTTON") (pin "3") (pinfunction "3_3") (pintype "passive"))
      (node (ref "CHANGE_BUTTON") (pin "4") (pinfunction "4_4") (pintype "passive"))
      (node (ref "R_CHANGE") (pin "1") (pinfunction "1_1") (pintype "passive"))
      (node (ref "U2") (pin "23") (pinfunction "IO15_23") (pintype "bidirectional"))
    )
    (net (code "21") (name "MISO") (class "Default")
      (node (ref "D12") (pin "1") (pinfunction "1_1") (pintype "passive"))
      (node (ref "J4") (pin "P7") (pinfunction "DAT0_P7") (pintype "bidirectional"))
      (node (ref "MISO") (pin "TP") (pinfunction "TP_TP") (pintype "input"))
      (node (ref "R8") (pin "1") (pinfunction "1_1") (pintype "passive"))
      (node (ref "U1") (pin "2") (pinfunction "DO(IO1)_2") (pintype "bidirectional"))
      (node (ref "U2") (pin "27") (pinfunction "IO2_27") (pintype "bidirectional"))
    )
    (net (code "22") (name "MOSI") (class "Default")
      (node (ref "D11") (pin "1") (pinfunction "1_1") (pintype "passive"))
      (node (ref "J1") (pin "14") (pinfunction "14_14") (pintype "bidirectional"))
      (node (ref "J4") (pin "P3") (pinfunction "CMD_P3") (pintype "bidirectional"))
      (node (ref "MOSI") (pin "TP") (pinfunction "TP_TP") (pintype "input"))
      (node (ref "R7") (pin "1") (pinfunction "1_1") (pintype "passive"))
      (node (ref "U1") (pin "5") (pinfunction "DI(IO0)_5") (pintype "bidirectional"))
      (node (ref "U2") (pin "7") (pinfunction "IO7_7") (pintype "bidirectional"))
    )
    (net (code "23") (name "Net-(CHG_LED-PadC)") (class "Default")
      (node (ref "CHG_LED") (pin "C") (pinfunction "C_C") (pintype "passive"))
      (node (ref "R1_BAT") (pin "1") (pinfunction "1_1") (pintype "passive"))
    )
    (net (code "24") (name "Net-(D3-K)") (class "Default")
      (node (ref "C4") (pin "1") (pinfunction "1_1") (pintype "passive"))
      (node (ref "D3") (pin "1") (pinfunction "K_1") (pintype "bidirectional"))
      (node (ref "D4") (pin "2") (pinfunction "A_2") (pintype "bidirectional"))
    )
    (net (code "25") (name "Net-(D7-CATHODE)") (class "Default")
      (node (ref "D7") (pin "1") (pinfunction "CATHODE_1") (pintype "bidirectional"))
      (node (ref "R_CAPACITOR") (pin "1") (pinfunction "1_1") (pintype "passive"))
    )
    (net (code "26") (name "Net-(EPD_C1-Pad2)") (class "Default")
      (node (ref "EPD_C1") (pin "2") (pinfunction "2_2") (pintype "passive"))
      (node (ref "J1") (pin "4") (pinfunction "4_4") (pintype "bidirectional"))
    )
    (net (code "27") (name "Net-(EPD_C2-Pad2)") (class "Default")
      (node (ref "EPD_C2") (pin "2") (pinfunction "2_2") (pintype "passive"))
      (node (ref "J1") (pin "5") (pinfunction "5_5") (pintype "bidirectional"))
    )
    (net (code "28") (name "Net-(EPD_C6-Pad2)") (class "Default")
      (node (ref "EPD_C6") (pin "2") (pinfunction "2_2") (pintype "passive"))
      (node (ref "J1") (pin "18") (pinfunction "18_18") (pintype "bidirectional"))
    )
    (net (code "29") (name "Net-(EPD_C7-Pad2)") (class "Default")
      (node (ref "EPD_C7") (pin "2") (pinfunction "2_2") (pintype "passive"))
      (node (ref "J1") (pin "19") (pinfunction "19_19") (pintype "bidirectional"))
    )
    (net (code "30") (name "Net-(EPD_C8-Pad2)") (class "Default")
      (node (ref "EPD_C8") (pin "2") (pinfunction "2_2") (pintype "passive"))
      (node (ref "J1") (pin "20") (pinfunction "20_20") (pintype "bidirectional"))
    )
    (net (code "31") (name "Net-(EPD_C10-Pad2)") (class "Default")
      (node (ref "EPD_C10") (pin "2") (pinfunction "2_2") (pintype "passive"))
      (node (ref "J1") (pin "22") (pinfunction "22_22") (pintype "bidirectional"))
    )
    (net (code "32") (name "Net-(EPD_C12-Pad2)") (class "Default")
      (node (ref "EPD_C12") (pin "2") (pinfunction "2_2") (pintype "passive"))
      (node (ref "J1") (pin "24") (pinfunction "24_24") (pintype "bidirectional"))
    )
    (net (code "33") (name "Net-(IC1-CT)") (class "Default")
      (node (ref "C_DELAY") (pin "1") (pinfunction "1_1") (pintype "passive"))
      (node (ref "IC1") (pin "5") (pinfunction "CT_5") (pintype "bidirectional"))
    )
    (net (code "34") (name "Net-(J2-PadA5)") (class "Default")
      (node (ref "J2") (pin "A5") (pinfunction "A5_A5") (pintype "bidirectional"))
      (node (ref "R2-USB1") (pin "2") (pinfunction "2_2") (pintype "passive"))
    )
    (net (code "35") (name "Net-(J2-PadB5)") (class "Default")
      (node (ref "J2") (pin "B5") (pinfunction "B5_B5") (pintype "bidirectional"))
      (node (ref "R2-USB") (pin "1") (pinfunction "1_1") (pintype "passive"))
    )
    (net (code "36") (name "Net-(MCP73831-PROG)") (class "Default")
      (node (ref "MCP73831") (pin "5") (pinfunction "PROG_5") (pintype "input"))
      (node (ref "R2_BAT") (pin "2") (pinfunction "2_2") (pintype "passive"))
    )
    (net (code "37") (name "Net-(MCP73831-STAT)") (class "Default")
      (node (ref "MCP73831") (pin "1") (pinfunction "STAT_1") (pintype "output"))
      (node (ref "R1_BAT") (pin "2") (pinfunction "2_2") (pintype "passive"))
    )
    (net (code "38") (name "PREVGH") (class "Default")
      (node (ref "D5") (pin "1") (pinfunction "K_1") (pintype "bidirectional"))
      (node (ref "EPD_C9") (pin "2") (pinfunction "2_2") (pintype "passive"))
      (node (ref "J1") (pin "21") (pinfunction "21_21") (pintype "bidirectional"))
    )
    (net (code "39") (name "PREVGL") (class "Default")
      (node (ref "D3") (pin "2") (pinfunction "A_2") (pintype "bidirectional"))
      (node (ref "EPD_C11") (pin "2") (pinfunction "2_2") (pintype "passive"))
      (node (ref "J1") (pin "23") (pinfunction "23_23") (pintype "bidirectional"))
    )
    (net (code "40") (name "RESE") (class "Default")
      (node (ref "J1") (pin "3") (pinfunction "3_3") (pintype "bidirectional"))
      (node (ref "Q3") (pin "2") (pinfunction "S_2") (pintype "bidirectional"))
      (node (ref "R3") (pin "2") (pinfunction "2_2") (pintype "passive"))
    )
    (net (code "41") (name "RESE'") (class "Default")
      (node (ref "R2") (pin "2") (pinfunction "2_2") (pintype "passive"))
      (node (ref "R3") (pin "1") (pinfunction "1_1") (pintype "passive"))
      (node (ref "SJ1") (pin "2") (pinfunction "2_2") (pintype "passive"))
    )
    (net (code "42") (name "RESET") (class "Default")
      (node (ref "C5") (pin "1") (pinfunction "1_1") (pintype "passive"))
      (node (ref "IC1") (pin "1") (pinfunction "VOUT_1") (pintype "bidirectional"))
      (node (ref "RESET_BUTTON") (pin "3") (pinfunction "3_3") (pintype "passive"))
      (node (ref "RESET_BUTTON") (pin "4") (pinfunction "4_4") (pintype "passive"))
      (node (ref "R_RESET") (pin "1") (pinfunction "1_1") (pintype "passive"))
      (node (ref "U2") (pin "3") (pinfunction "EN_3") (pintype "input"))
    )
    (net (code "43") (name "RTC_RST") (class "Default")
      (node (ref "U2") (pin "16") (pinfunction "IO18_16") (pintype "bidirectional"))
      (node (ref "U3") (pin "4") (pinfunction "~{RST}_4") (pintype "input"))
    )
    (net (code "44") (name "RX") (class "Default")
      (node (ref "RX") (pin "TP") (pinfunction "TP_TP") (pintype "input"))
      (node (ref "U2") (pin "24") (pinfunction "RXD0/GPIO17_24") (pintype "bidirectional"))
    )
    (net (code "45") (name "SCK") (class "Default")
      (node (ref "D10") (pin "1") (pinfunction "1_1") (pintype "passive"))
      (node (ref "J1") (pin "13") (pinfunction "13_13") (pintype "bidirectional"))
      (node (ref "J4") (pin "P5") (pinfunction "CLK_P5") (pintype "bidirectional"))
      (node (ref "R6") (pin "1") (pinfunction "1_1") (pintype "passive"))
      (node (ref "SCK") (pin "TP") (pinfunction "TP_TP") (pintype "input"))
      (node (ref "U1") (pin "6") (pinfunction "CLK_6") (pintype "input"))
      (node (ref "U2") (pin "6") (pinfunction "IO6_6") (pintype "bidirectional"))
    )
    (net (code "46") (name "SCL") (class "Default")
      (node (ref "J3") (pin "4") (pinfunction "4_4") (pintype "passive"))
      (node (ref "R2-PINH") (pin "1") (pinfunction "1_1") (pintype "passive"))
      (node (ref "SENSOR2") (pin "4") (pinfunction "SCK_4") (pintype "input"))
      (node (ref "U2") (pin "20") (pinfunction "IO22_20") (pintype "bidirectional"))
      (node (ref "U3") (pin "16") (pinfunction "SCL_16") (pintype "input"))
      (node (ref "U4") (pin "7") (pinfunction "SCL_7") (pintype "input"))
    )
    (net (code "47") (name "SDA") (class "Default")
      (node (ref "J3") (pin "3") (pinfunction "3_3") (pintype "passive"))
      (node (ref "R1_PINH") (pin "1") (pinfunction "1_1") (pintype "passive"))
      (node (ref "SENSOR2") (pin "3") (pinfunction "SDI_3") (pintype "bidirectional"))
      (node (ref "U2") (pin "19") (pinfunction "IO21_19") (pintype "bidirectional"))
      (node (ref "U3") (pin "15") (pinfunction "SDA_15") (pintype "bidirectional"))
      (node (ref "U4") (pin "8") (pinfunction "SDA_8") (pintype "bidirectional"))
    )
    (net (code "48") (name "SRC") (class "Default")
      (node (ref "C4") (pin "2") (pinfunction "2_2") (pintype "passive"))
      (node (ref "D5") (pin "2") (pinfunction "A_2") (pintype "bidirectional"))
      (node (ref "L1") (pin "1") (pinfunction "1_1") (pintype "passive"))
      (node (ref "Q3") (pin "3") (pinfunction "D_3") (pintype "bidirectional"))
    )
    (net (code "49") (name "SS_SD") (class "Default")
      (node (ref "D8") (pin "1") (pinfunction "1_1") (pintype "passive"))
      (node (ref "J4") (pin "P2") (pinfunction "CD/DAT3_P2") (pintype "bidirectional"))
      (node (ref "R10") (pin "1") (pinfunction "1_1") (pintype "passive"))
      (node (ref "U2") (pin "4") (pinfunction "IO4_4") (pintype "bidirectional"))
    )
    (net (code "50") (name "TX") (class "Default")
      (node (ref "TX") (pin "TP") (pinfunction "TP_TP") (pintype "input"))
      (node (ref "U2") (pin "25") (pinfunction "TXD0/GPIO16_25") (pintype "bidirectional"))
    )
    (net (code "51") (name "USB_D+") (class "Default")
      (node (ref "D1") (pin "1") (pinfunction "I/O1_1_1") (pintype "bidirectional"))
      (node (ref "U2") (pin "14") (pinfunction "IO13_14") (pintype "bidirectional"))
    )
    (net (code "52") (name "USB_D-") (class "Default")
      (node (ref "D1") (pin "3") (pinfunction "I/O2_1_3") (pintype "bidirectional"))
      (node (ref "U2") (pin "13") (pinfunction "IO12_13") (pintype "bidirectional"))
    )
    (net (code "53") (name "VBAT") (class "Default")
      (node (ref "C2_BAT") (pin "1") (pinfunction "1_1") (pintype "passive"))
      (node (ref "MCP73831") (pin "3") (pinfunction "VBAT_3") (pintype "power_in"))
      (node (ref "Q1") (pin "3") (pinfunction "D_3") (pintype "bidirectional"))
      (node (ref "U4") (pin "2") (pinfunction "CELL_2") (pintype "power_in"))
      (node (ref "U4") (pin "3") (pinfunction "VDD_3") (pintype "power_in"))
      (node (ref "VBAT") (pin "TP") (pinfunction "TP_TP") (pintype "input"))
    )
    (net (code "54") (name "VBUS") (class "Default")
      (node (ref "C1_BAT") (pin "1") (pinfunction "1_1") (pintype "passive"))
      (node (ref "C4_USB") (pin "1") (pinfunction "1_1") (pintype "passive"))
      (node (ref "C5_USB") (pin "1") (pinfunction "1_1") (pintype "passive"))
      (node (ref "CHG_LED") (pin "A") (pinfunction "A_A") (pintype "passive"))
      (node (ref "D1") (pin "5") (pinfunction "VBUS_5") (pintype "bidirectional"))
      (node (ref "D2") (pin "2") (pinfunction "ANODE_2") (pintype "bidirectional"))
      (node (ref "MCP73831") (pin "4") (pinfunction "VIN_4") (pintype "power_in"))
      (node (ref "PFMF.050.1") (pin "2") (pinfunction "2_2") (pintype "passive"))
      (node (ref "Q1") (pin "1") (pinfunction "G_1") (pintype "bidirectional"))
      (node (ref "R1_PWRUSB") (pin "2") (pinfunction "2_2") (pintype "passive"))
      (node (ref "VBUS") (pin "TP") (pinfunction "TP_TP") (pintype "input"))
    )
    (net (code "55") (name "VRTC") (class "Default")
      (node (ref "C10_SUPERCAP") (pin "1") (pinfunction "1_1") (pintype "passive"))
      (node (ref "C8") (pin "1") (pinfunction "1_1") (pintype "passive"))
      (node (ref "R_CAPACITOR") (pin "2") (pinfunction "2_2") (pintype "passive"))
      (node (ref "U3") (pin "14") (pinfunction "VBAT_14") (pintype "power_in"))
    )
    (net (code "56") (name "VUSB") (class "Default")
      (node (ref "J2") (pin "A4") (pinfunction "A4_A4") (pintype "bidirectional"))
      (node (ref "J2") (pin "A9") (pinfunction "A9_A9") (pintype "bidirectional"))
      (node (ref "J2") (pin "B4") (pinfunction "B4_B4") (pintype "bidirectional"))
      (node (ref "J2") (pin "B9") (pinfunction "B9_B9") (pintype "bidirectional"))
      (node (ref "PFMF.050.1") (pin "1") (pinfunction "1_1") (pintype "passive"))
    )
    (net (code "57") (name "unconnected-(IC1-NC-Pad4)") (class "Default")
      (node (ref "IC1") (pin "4") (pinfunction "NC_4") (pintype "no_connect"))
    )
    (net (code "58") (name "unconnected-(IC4-NC-Pad4)") (class "Default")
      (node (ref "IC4") (pin "4") (pinfunction "NC_4") (pintype "no_connect"))
    )
    (net (code "59") (name "unconnected-(J1-Pad1)") (class "Default")
      (node (ref "J1") (pin "1") (pinfunction "1_1") (pintype "bidirectional"))
    )
    (net (code "60") (name "unconnected-(J1-Pad6)") (class "Default")
      (node (ref "J1") (pin "6") (pinfunction "6_6") (pintype "bidirectional"))
    )
    (net (code "61") (name "unconnected-(J1-Pad7)") (class "Default")
      (node (ref "J1") (pin "7") (pinfunction "7_7") (pintype "bidirectional"))
    )
    (net (code "62") (name "unconnected-(J2-PadA8)") (class "Default")
      (node (ref "J2") (pin "A8") (pinfunction "A8_A8") (pintype "bidirectional"))
    )
    (net (code "63") (name "unconnected-(J2-PadB8)") (class "Default")
      (node (ref "J2") (pin "B8") (pinfunction "B8_B8") (pintype "bidirectional"))
    )
    (net (code "64") (name "unconnected-(J4-DAT1-PadP8)") (class "Default")
      (node (ref "J4") (pin "P8") (pinfunction "DAT1_P8") (pintype "bidirectional"))
    )
    (net (code "65") (name "unconnected-(J4-DAT2-PadP1)") (class "Default")
      (node (ref "J4") (pin "P1") (pinfunction "DAT2_P1") (pintype "bidirectional"))
    )
    (net (code "66") (name "unconnected-(J4-DETECTION_1-PadS1)") (class "Default")
      (node (ref "J4") (pin "S1") (pinfunction "DETECTION_1_S1") (pintype "bidirectional"))
    )
    (net (code "67") (name "unconnected-(J4-DETECTION_2-PadS2)") (class "Default")
      (node (ref "J4") (pin "S2") (pinfunction "DETECTION_2_S2") (pintype "bidirectional"))
    )
    (net (code "68") (name "unconnected-(U2-NC-Pad22)") (class "Default")
      (node (ref "U2") (pin "22") (pinfunction "NC_22") (pintype "no_connect"))
    )
    (net (code "69") (name "unconnected-(U4-~{ALERT}-Pad5)") (class "Default")
      (node (ref "U4") (pin "5") (pinfunction "~{ALERT}_5") (pintype "output"))
    )
  )
)
